# ProDoc_ChisFlash-MBC5-MAX-v1_22_32M.net
KiCad netlist of a schematic drawn in EasyEDA Pro
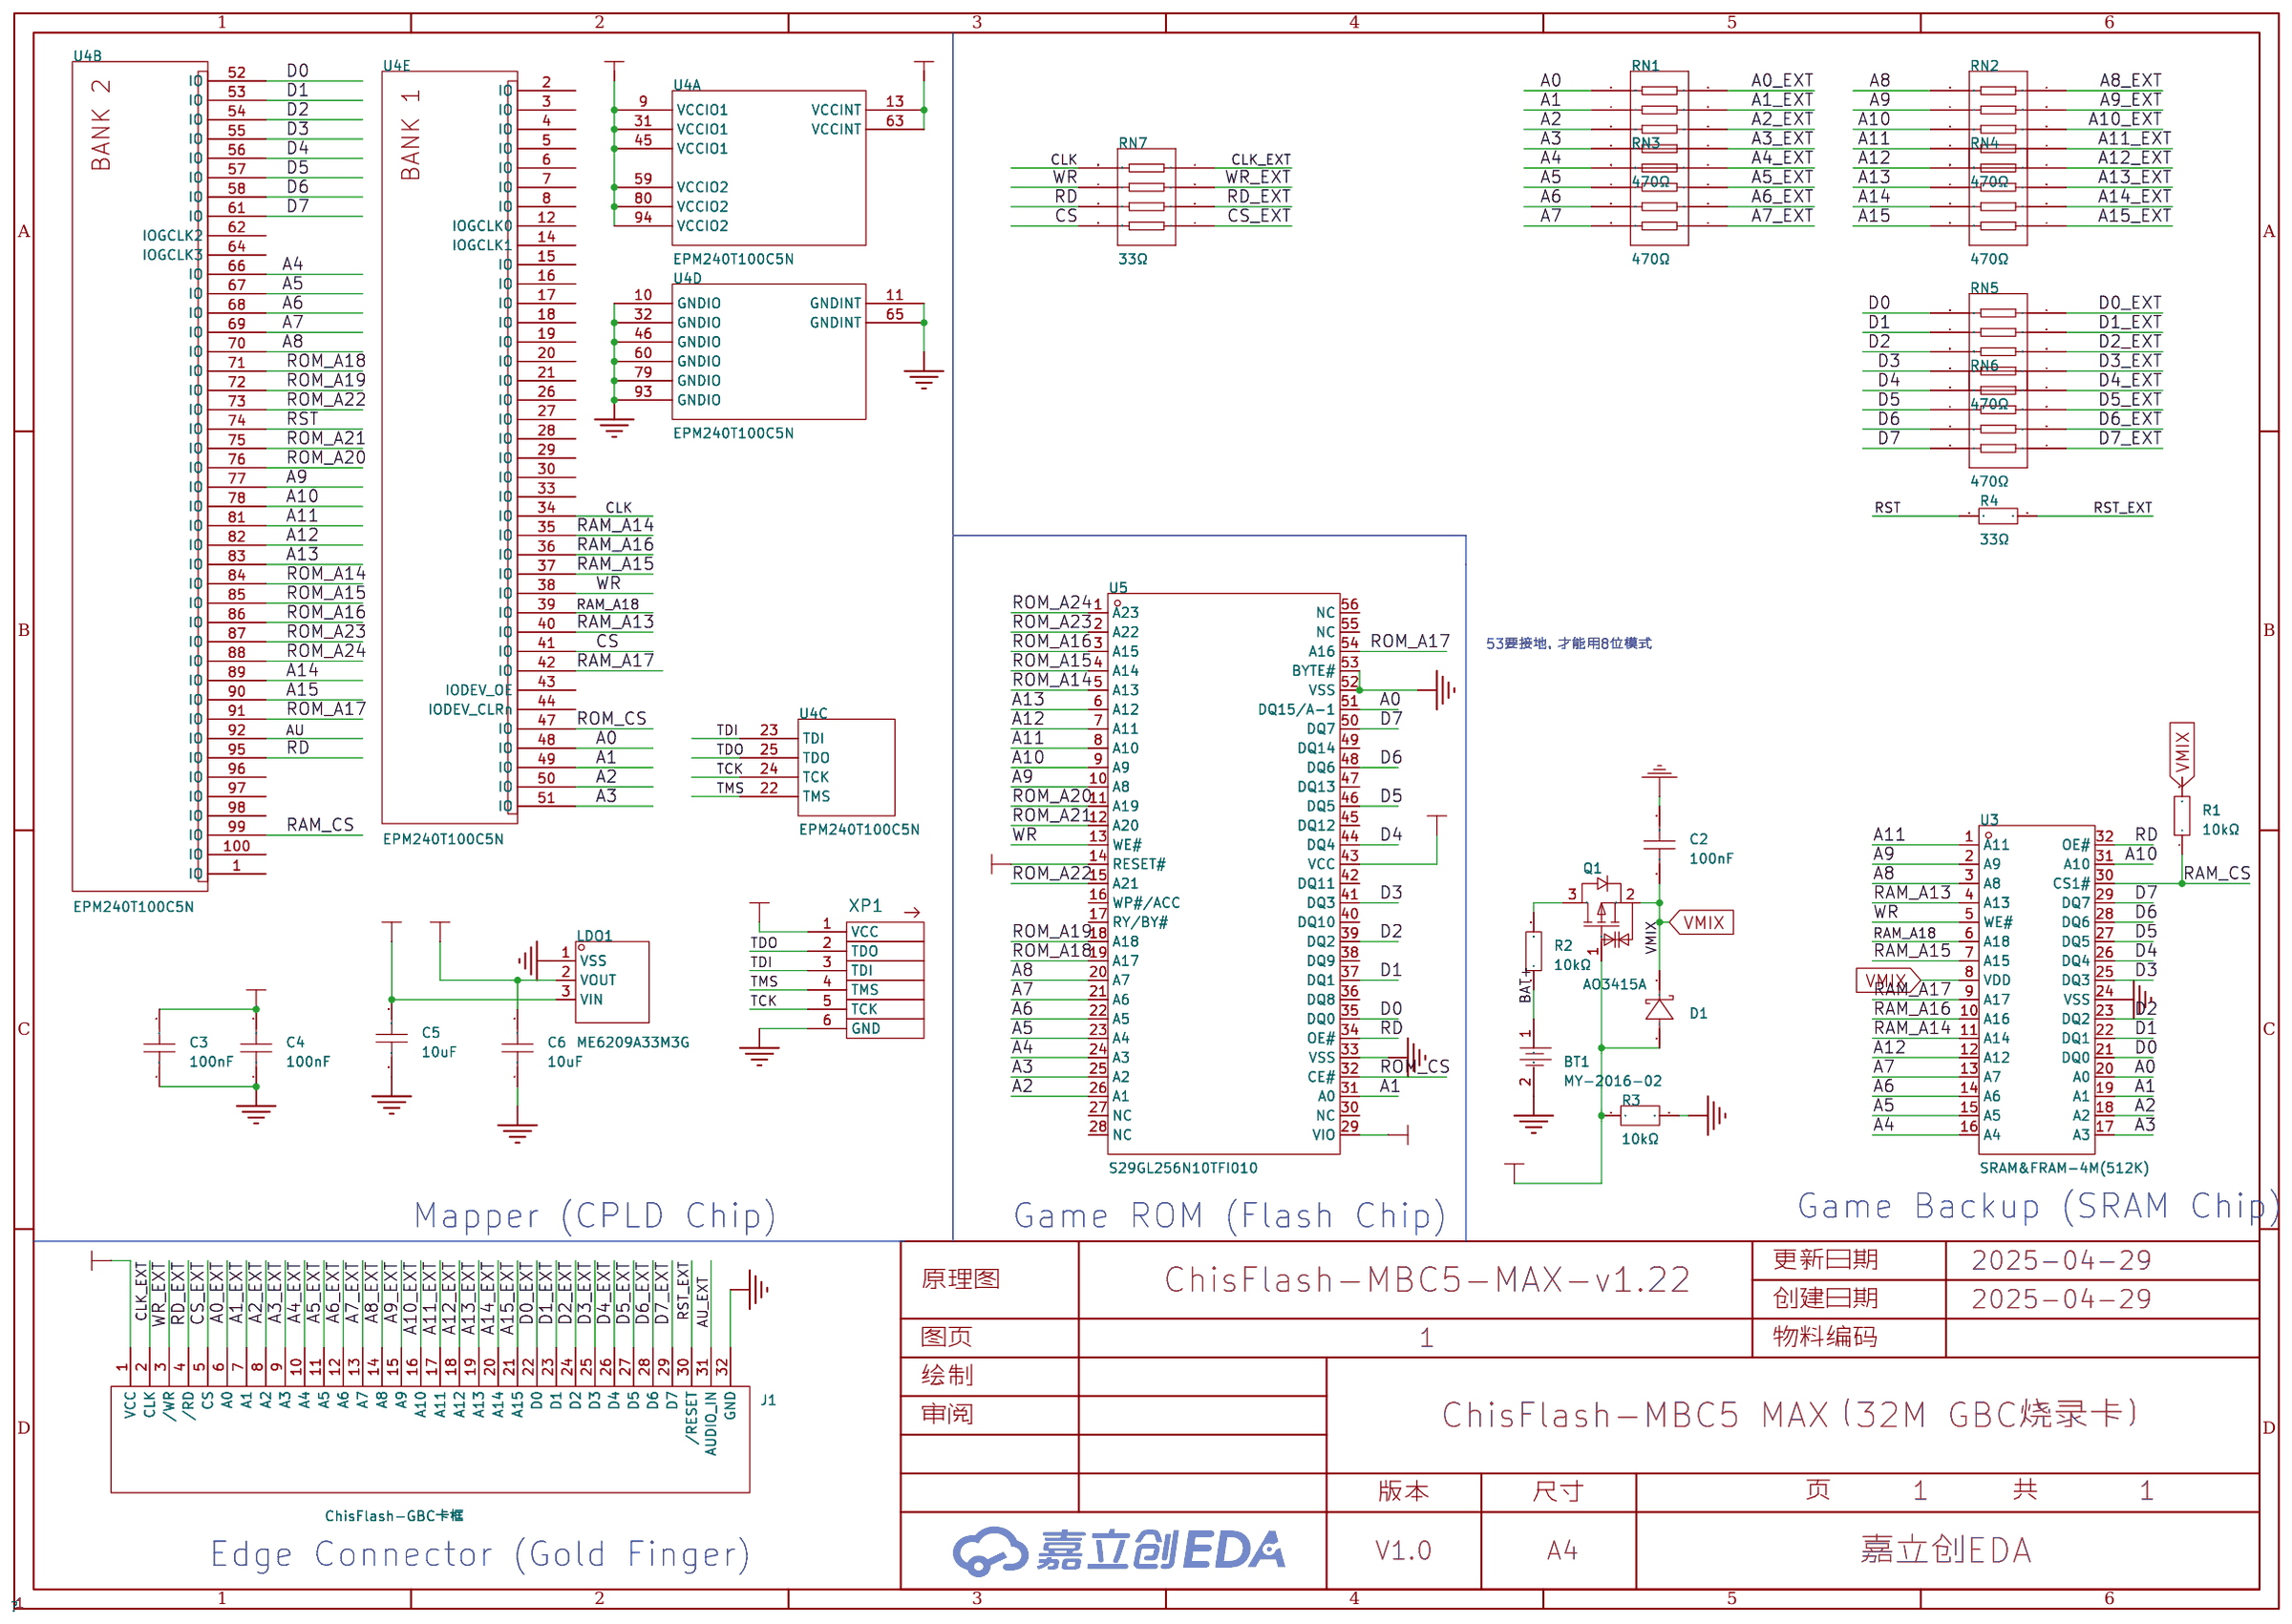
[diagram p0: schematic sheet]

(export (version "E")
  (design (tool "Eeschema 10.0.6"))
  (components
    (comp (ref "BT1")
      (value "MY-2016-02")
      (footprint "easyedapro:BAT-SMD_MY-2032-08")
      (description "连接器类型:电池扣;适用电池规格:CR2016;触头材质:磷青铜;触点电镀:镍;工作温度范围:-25°C~+85°C;")
      (fields (field (name "Manufacturer") "MYOUNG(美阳)"))
      (libsource (lib "easyedapro") (part "MY-2016-02"))
    )
    (comp (ref "C2")
      (value "100nF")
      (footprint "easyedapro:C0603")
      (description "容值:100nF;精度:±10%;额定电压:50V;材质(温度系数):X7R;")
      (fields
        (field (name "Manufacturer Part") "CGA0603X7R104K500JT")
        (field (name "Manufacturer") "HRE(芯声)")
      )
      (libsource (lib "easyedapro") (part "CGA0603X7R104K500JT"))
    )
    (comp (ref "C3")
      (value "100nF")
      (footprint "easyedapro:C0603")
      (description "容值:100nF;精度:±10%;额定电压:50V;材质(温度系数):X7R;")
      (fields
        (field (name "Manufacturer Part") "CGA0603X7R104K500JT")
        (field (name "Manufacturer") "HRE(芯声)")
      )
      (libsource (lib "easyedapro") (part "CGA0603X7R104K500JT"))
    )
    (comp (ref "C4")
      (value "100nF")
      (footprint "easyedapro:C0603")
      (description "容值:100nF;精度:±10%;额定电压:50V;材质(温度系数):X7R;")
      (fields
        (field (name "Manufacturer Part") "CGA0603X7R104K500JT")
        (field (name "Manufacturer") "HRE(芯声)")
      )
      (libsource (lib "easyedapro") (part "CGA0603X7R104K500JT"))
    )
    (comp (ref "C5")
      (value "10uF")
      (footprint "easyedapro:C0603")
      (description "容值:10uF;精度:±20%;额定电压:25V;材质(温度系数):X5R;")
      (fields
        (field (name "Manufacturer Part") "CL10A106MA8NRNC")
        (field (name "Manufacturer") "SAMSUNG(三星)")
      )
      (libsource (lib "easyedapro") (part "CL10A106MA8NRNC"))
    )
    (comp (ref "C6")
      (value "10uF")
      (footprint "easyedapro:C0603")
      (description "容值:10uF;精度:±20%;额定电压:25V;材质(温度系数):X5R;")
      (fields
        (field (name "Manufacturer Part") "CL10A106MA8NRNC")
        (field (name "Manufacturer") "SAMSUNG(三星)")
      )
      (libsource (lib "easyedapro") (part "CL10A106MA8NRNC"))
    )
    (comp (ref "D1")
      (value "RB751V-40")
      (footprint "easyedapro:SOD-323_L1.7-W1.3-LS2.6-RD-1")
      (description "二极管配置:独立式;正向压降(Vf):370mV@1mA;直流反向耐压(Vr):40V;平均整流电流(Io):30mA;")
      (fields (field (name "Manufacturer") "宏迦橙"))
      (libsource (lib "easyedapro") (part "RB751V-40_C7502691"))
    )
    (comp (ref "J1")
      (value "ChisFlash-GBC卡框")
      (footprint "easyedapro:ChisFlash-GBC卡框")
      (libsource (lib "easyedapro") (part "ChisFlash-GBC卡框"))
    )
    (comp (ref "LDO1")
      (value "ME6209A33M3G")
      (footprint "easyedapro:SOT-23-3_L2.9-W1.6-P1.90-LS2.8-BR")
      (description "输出类型:固定;最大输入电压:18V;输出电压:3.3V;最大输出电流:250mA;电源纹波抑制比(PSRR):-;输出极性:正极;")
      (fields (field (name "Manufacturer") "MICRONE(南京微盟)"))
      (libsource (lib "easyedapro") (part "ME6209A33M3G"))
    )
    (comp (ref "Q1")
      (value "AO3415A")
      (footprint "easyedapro:SOT-23-3_L3.0-W1.7-P0.95-LS2.9-BR")
      (fields (field (name "Manufacturer") "UMW(友台半导体)"))
      (libsource (lib "easyedapro") (part "AO3415A_C347479"))
    )
    (comp (ref "R1")
      (value "10kΩ")
      (footprint "easyedapro:R0603")
      (description "电阻类型:厚膜电阻;阻值:10kΩ;精度:±1%;功率:100mW;温度系数:±100ppm/°C;最大工作电压:75V;工作温度范围:-55°C~+155°C;")
      (fields
        (field (name "Manufacturer Part") "0603WAF1002T5E")
        (field (name "Manufacturer") "UNI-ROYAL(厚声)")
      )
      (libsource (lib "easyedapro") (part "0603WAF1002T5E"))
    )
    (comp (ref "R2")
      (value "10kΩ")
      (footprint "easyedapro:R0603")
      (description "电阻类型:厚膜电阻;阻值:10kΩ;精度:±1%;功率:100mW;温度系数:±100ppm/°C;最大工作电压:75V;工作温度范围:-55°C~+155°C;")
      (fields
        (field (name "Manufacturer Part") "0603WAF1002T5E")
        (field (name "Manufacturer") "UNI-ROYAL(厚声)")
      )
      (libsource (lib "easyedapro") (part "0603WAF1002T5E"))
    )
    (comp (ref "R3")
      (value "10kΩ")
      (footprint "easyedapro:R0603")
      (description "电阻类型:薄膜电阻;阻值:10kΩ;精度:±0.1%;功率:100mW;最大工作电压:75V;温度系数:±25ppm/°C;")
      (fields (field (name "Manufacturer Part") "RT0603BRD1010KL") (field (name "Manufacturer") "YAGEO(国巨)"))
      (libsource (lib "easyedapro") (part "RT0603BRD1010KL"))
    )
    (comp (ref "R4")
      (value "33Ω")
      (footprint "easyedapro:R0603")
      (description "电阻类型:厚膜电阻;阻值:33Ω;精度:±1%;功率:100mW;最大工作电压:75V;温度系数:±100ppm/°C;")
      (fields
        (field (name "Manufacturer Part") "0603WAF330JT5E")
        (field (name "Manufacturer") "UNI-ROYAL(厚声)")
      )
      (libsource (lib "easyedapro") (part "0603WAF330JT5E"))
    )
    (comp (ref "RN1")
      (value "470Ω")
      (footprint "easyedapro:RES-ARRAY-SMD_0603-8P-L3.2-W1.6-BL")
      (description "电阻器数:4;阻值:470Ω;精度:±5%;单个元件功率:62.5mW;温度系数:±200ppm/°C;")
      (fields
        (field (name "Manufacturer Part") "4D03WGJ0471T5E")
        (field (name "Manufacturer") "UNI-ROYAL(厚声)")
      )
      (libsource (lib "easyedapro") (part "4D03WGJ0471T5E"))
    )
    (comp (ref "RN2")
      (value "470Ω")
      (footprint "easyedapro:RES-ARRAY-SMD_0603-8P-L3.2-W1.6-BL")
      (description "电阻器数:4;阻值:470Ω;精度:±5%;单个元件功率:62.5mW;温度系数:±200ppm/°C;")
      (fields
        (field (name "Manufacturer Part") "4D03WGJ0471T5E")
        (field (name "Manufacturer") "UNI-ROYAL(厚声)")
      )
      (libsource (lib "easyedapro") (part "4D03WGJ0471T5E"))
    )
    (comp (ref "RN3")
      (value "470Ω")
      (footprint "easyedapro:RES-ARRAY-SMD_0603-8P-L3.2-W1.6-BL")
      (description "电阻器数:4;阻值:470Ω;精度:±5%;单个元件功率:62.5mW;温度系数:±200ppm/°C;")
      (fields
        (field (name "Manufacturer Part") "4D03WGJ0471T5E")
        (field (name "Manufacturer") "UNI-ROYAL(厚声)")
      )
      (libsource (lib "easyedapro") (part "4D03WGJ0471T5E"))
    )
    (comp (ref "RN4")
      (value "470Ω")
      (footprint "easyedapro:RES-ARRAY-SMD_0603-8P-L3.2-W1.6-BL")
      (description "电阻器数:4;阻值:470Ω;精度:±5%;单个元件功率:62.5mW;温度系数:±200ppm/°C;")
      (fields
        (field (name "Manufacturer Part") "4D03WGJ0471T5E")
        (field (name "Manufacturer") "UNI-ROYAL(厚声)")
      )
      (libsource (lib "easyedapro") (part "4D03WGJ0471T5E"))
    )
    (comp (ref "RN5")
      (value "470Ω")
      (footprint "easyedapro:RES-ARRAY-SMD_0603-8P-L3.2-W1.6-BL")
      (description "电阻器数:4;阻值:470Ω;精度:±5%;单个元件功率:62.5mW;温度系数:±200ppm/°C;")
      (fields
        (field (name "Manufacturer Part") "4D03WGJ0471T5E")
        (field (name "Manufacturer") "UNI-ROYAL(厚声)")
      )
      (libsource (lib "easyedapro") (part "4D03WGJ0471T5E"))
    )
    (comp (ref "RN6")
      (value "470Ω")
      (footprint "easyedapro:RES-ARRAY-SMD_0603-8P-L3.2-W1.6-BL")
      (description "电阻器数:4;阻值:470Ω;精度:±5%;单个元件功率:62.5mW;温度系数:±200ppm/°C;")
      (fields
        (field (name "Manufacturer Part") "4D03WGJ0471T5E")
        (field (name "Manufacturer") "UNI-ROYAL(厚声)")
      )
      (libsource (lib "easyedapro") (part "4D03WGJ0471T5E"))
    )
    (comp (ref "RN7")
      (value "33Ω")
      (footprint "easyedapro:RES-ARRAY-SMD_0603-8P-L3.2-W1.6-BL")
      (description "电阻器数:4;阻值:470Ω;精度:±5%;单个元件功率:62.5mW;温度系数:±200ppm/°C;")
      (fields
        (field (name "Manufacturer Part") "4D03WGF330JT5E")
        (field (name "Manufacturer") "UNI-ROYAL(厚声)")
      )
      (libsource (lib "easyedapro") (part "4D03WGJ0471T5E"))
    )
    (comp (ref "U3")
      (value "SRAM&FRAM-4M(512K)")
      (footprint "easyedapro:TSSOP-TSOP二合一_1")
      (libsource (lib "easyedapro") (part "SRAM&FRAM-4M(512K)"))
    )
    (comp (ref "U4")
      (value "EPM240T100C5N")
      (footprint "easyedapro:TQFP-100_L14.0-W14.0-P0.50-LS16.0-BL")
      (description "类型:其它PLD;逻辑门数量:-;逻辑单元数:-;逻辑阵列块数:240;")
      (fields (field (name "Manufacturer") "Intel/Altera"))
      (libsource (lib "easyedapro") (part "EPM240T100C5N"))
    )
    (comp (ref "U5")
      (value "S29GL256N10TFI010")
      (footprint "easyedapro:TSOP-56_L18.4-W14.0-P0.50-LS20.0-TL")
      (libsource (lib "easyedapro") (part "S29GL256N10TFI010"))
    )
    (comp (ref "XP1")
      (value "JTAG")
      (footprint "easyedapro:HDR-TH_6P-P1.27-V-M-1")
      (libsource (lib "easyedapro") (part "jtag"))
    )
  )
  (nets
    (net (code "1") (name "+3V3") (class "Default")
      (node (ref "C3") (pin "2") (pinfunction "2_2") (pintype "unspecified"))
      (node (ref "C4") (pin "2") (pinfunction "2_2") (pintype "unspecified"))
      (node (ref "C6") (pin "2") (pinfunction "2_2") (pintype "unspecified"))
      (node (ref "D1") (pin "2") (pinfunction "A_2") (pintype "unspecified"))
      (node (ref "LDO1") (pin "2") (pinfunction "VOUT_2") (pintype "unspecified"))
      (node (ref "Q1") (pin "1") (pinfunction "G_1") (pintype "unspecified"))
      (node (ref "R3") (pin "1") (pinfunction "1_1") (pintype "unspecified"))
      (node (ref "U4") (pin "13") (pinfunction "VCCINT_13") (pintype "unspecified"))
      (node (ref "U4") (pin "31") (pinfunction "VCCIO1_31") (pintype "unspecified"))
      (node (ref "U4") (pin "45") (pinfunction "VCCIO1_45") (pintype "unspecified"))
      (node (ref "U4") (pin "59") (pinfunction "VCCIO2_59") (pintype "unspecified"))
      (node (ref "U4") (pin "63") (pinfunction "VCCINT_63") (pintype "unspecified"))
      (node (ref "U4") (pin "80") (pinfunction "VCCIO2_80") (pintype "unspecified"))
      (node (ref "U4") (pin "9") (pinfunction "VCCIO1_9") (pintype "unspecified"))
      (node (ref "U4") (pin "94") (pinfunction "VCCIO2_94") (pintype "unspecified"))
      (node (ref "U5") (pin "14") (pinfunction "RESET#_14") (pintype "unspecified"))
      (node (ref "U5") (pin "29") (pinfunction "VIO_29") (pintype "unspecified"))
      (node (ref "U5") (pin "43") (pinfunction "VCC_43") (pintype "unspecified"))
      (node (ref "XP1") (pin "1") (pinfunction "VCC_1") (pintype "output"))
    )
    (net (code "2") (name "+5V") (class "Default")
      (node (ref "C5") (pin "2") (pinfunction "2_2") (pintype "unspecified"))
      (node (ref "J1") (pin "1") (pinfunction "VCC_1") (pintype "unspecified"))
      (node (ref "LDO1") (pin "3") (pinfunction "VIN_3") (pintype "unspecified"))
    )
    (net (code "3") (name "/A0") (class "Default")
      (node (ref "RN1") (pin "8") (pinfunction "8_8") (pintype "input"))
      (node (ref "U3") (pin "20") (pinfunction "A0_20") (pintype "unspecified"))
      (node (ref "U4") (pin "48") (pinfunction "IO_48") (pintype "bidirectional"))
      (node (ref "U5") (pin "51") (pinfunction "DQ15/A-1_51") (pintype "unspecified"))
    )
    (net (code "4") (name "/A0_EXT") (class "Default")
      (node (ref "J1") (pin "6") (pinfunction "A0_6") (pintype "unspecified"))
      (node (ref "RN1") (pin "1") (pinfunction "1_1") (pintype "input"))
    )
    (net (code "5") (name "/A1") (class "Default")
      (node (ref "RN1") (pin "7") (pinfunction "7_7") (pintype "input"))
      (node (ref "U3") (pin "19") (pinfunction "A1_19") (pintype "unspecified"))
      (node (ref "U4") (pin "49") (pinfunction "IO_49") (pintype "bidirectional"))
      (node (ref "U5") (pin "31") (pinfunction "A0_31") (pintype "unspecified"))
    )
    (net (code "6") (name "/A1_EXT") (class "Default")
      (node (ref "J1") (pin "7") (pinfunction "A1_7") (pintype "unspecified"))
      (node (ref "RN1") (pin "2") (pinfunction "2_2") (pintype "input"))
    )
    (net (code "7") (name "/A2") (class "Default")
      (node (ref "RN1") (pin "6") (pinfunction "6_6") (pintype "input"))
      (node (ref "U3") (pin "18") (pinfunction "A2_18") (pintype "unspecified"))
      (node (ref "U4") (pin "50") (pinfunction "IO_50") (pintype "bidirectional"))
      (node (ref "U5") (pin "26") (pinfunction "A1_26") (pintype "unspecified"))
    )
    (net (code "8") (name "/A2_EXT") (class "Default")
      (node (ref "J1") (pin "8") (pinfunction "A2_8") (pintype "unspecified"))
      (node (ref "RN1") (pin "3") (pinfunction "3_3") (pintype "input"))
    )
    (net (code "9") (name "/A3") (class "Default")
      (node (ref "RN1") (pin "5") (pinfunction "5_5") (pintype "input"))
      (node (ref "U3") (pin "17") (pinfunction "A3_17") (pintype "unspecified"))
      (node (ref "U4") (pin "51") (pinfunction "IO_51") (pintype "bidirectional"))
      (node (ref "U5") (pin "25") (pinfunction "A2_25") (pintype "unspecified"))
    )
    (net (code "10") (name "/A3_EXT") (class "Default")
      (node (ref "J1") (pin "9") (pinfunction "A3_9") (pintype "unspecified"))
      (node (ref "RN1") (pin "4") (pinfunction "4_4") (pintype "input"))
    )
    (net (code "11") (name "/A4") (class "Default")
      (node (ref "RN3") (pin "8") (pinfunction "8_8") (pintype "input"))
      (node (ref "U3") (pin "16") (pinfunction "A4_16") (pintype "unspecified"))
      (node (ref "U4") (pin "66") (pinfunction "IO_66") (pintype "bidirectional"))
      (node (ref "U5") (pin "24") (pinfunction "A3_24") (pintype "unspecified"))
    )
    (net (code "12") (name "/A4_EXT") (class "Default")
      (node (ref "J1") (pin "10") (pinfunction "A4_10") (pintype "unspecified"))
      (node (ref "RN3") (pin "1") (pinfunction "1_1") (pintype "input"))
    )
    (net (code "13") (name "/A5") (class "Default")
      (node (ref "RN3") (pin "7") (pinfunction "7_7") (pintype "input"))
      (node (ref "U3") (pin "15") (pinfunction "A5_15") (pintype "unspecified"))
      (node (ref "U4") (pin "67") (pinfunction "IO_67") (pintype "bidirectional"))
      (node (ref "U5") (pin "23") (pinfunction "A4_23") (pintype "unspecified"))
    )
    (net (code "14") (name "/A5_EXT") (class "Default")
      (node (ref "J1") (pin "11") (pinfunction "A5_11") (pintype "unspecified"))
      (node (ref "RN3") (pin "2") (pinfunction "2_2") (pintype "input"))
    )
    (net (code "15") (name "/A6") (class "Default")
      (node (ref "RN3") (pin "6") (pinfunction "6_6") (pintype "input"))
      (node (ref "U3") (pin "14") (pinfunction "A6_14") (pintype "unspecified"))
      (node (ref "U4") (pin "68") (pinfunction "IO_68") (pintype "bidirectional"))
      (node (ref "U5") (pin "22") (pinfunction "A5_22") (pintype "unspecified"))
    )
    (net (code "16") (name "/A6_EXT") (class "Default")
      (node (ref "J1") (pin "12") (pinfunction "A6_12") (pintype "unspecified"))
      (node (ref "RN3") (pin "3") (pinfunction "3_3") (pintype "input"))
    )
    (net (code "17") (name "/A7") (class "Default")
      (node (ref "RN3") (pin "5") (pinfunction "5_5") (pintype "input"))
      (node (ref "U3") (pin "13") (pinfunction "A7_13") (pintype "unspecified"))
      (node (ref "U4") (pin "69") (pinfunction "IO_69") (pintype "bidirectional"))
      (node (ref "U5") (pin "21") (pinfunction "A6_21") (pintype "unspecified"))
    )
    (net (code "18") (name "/A7_EXT") (class "Default")
      (node (ref "J1") (pin "13") (pinfunction "A7_13") (pintype "unspecified"))
      (node (ref "RN3") (pin "4") (pinfunction "4_4") (pintype "input"))
    )
    (net (code "19") (name "/A8") (class "Default")
      (node (ref "RN2") (pin "8") (pinfunction "8_8") (pintype "input"))
      (node (ref "U3") (pin "3") (pinfunction "A8_3") (pintype "unspecified"))
      (node (ref "U4") (pin "70") (pinfunction "IO_70") (pintype "bidirectional"))
      (node (ref "U5") (pin "20") (pinfunction "A7_20") (pintype "unspecified"))
    )
    (net (code "20") (name "/A8_EXT") (class "Default")
      (node (ref "J1") (pin "14") (pinfunction "A8_14") (pintype "unspecified"))
      (node (ref "RN2") (pin "1") (pinfunction "1_1") (pintype "input"))
    )
    (net (code "21") (name "/A9") (class "Default")
      (node (ref "RN2") (pin "7") (pinfunction "7_7") (pintype "input"))
      (node (ref "U3") (pin "2") (pinfunction "A9_2") (pintype "unspecified"))
      (node (ref "U4") (pin "77") (pinfunction "IO_77") (pintype "bidirectional"))
      (node (ref "U5") (pin "10") (pinfunction "A8_10") (pintype "unspecified"))
    )
    (net (code "22") (name "/A9_EXT") (class "Default")
      (node (ref "J1") (pin "15") (pinfunction "A9_15") (pintype "unspecified"))
      (node (ref "RN2") (pin "2") (pinfunction "2_2") (pintype "input"))
    )
    (net (code "23") (name "/A10") (class "Default")
      (node (ref "RN2") (pin "6") (pinfunction "6_6") (pintype "input"))
      (node (ref "U3") (pin "31") (pinfunction "A10_31") (pintype "unspecified"))
      (node (ref "U4") (pin "78") (pinfunction "IO_78") (pintype "bidirectional"))
      (node (ref "U5") (pin "9") (pinfunction "A9_9") (pintype "unspecified"))
    )
    (net (code "24") (name "/A10_EXT") (class "Default")
      (node (ref "J1") (pin "16") (pinfunction "A10_16") (pintype "unspecified"))
      (node (ref "RN2") (pin "3") (pinfunction "3_3") (pintype "input"))
    )
    (net (code "25") (name "/A11") (class "Default")
      (node (ref "RN2") (pin "5") (pinfunction "5_5") (pintype "input"))
      (node (ref "U3") (pin "1") (pinfunction "A11_1") (pintype "unspecified"))
      (node (ref "U4") (pin "81") (pinfunction "IO_81") (pintype "bidirectional"))
      (node (ref "U5") (pin "8") (pinfunction "A10_8") (pintype "unspecified"))
    )
    (net (code "26") (name "/A11_EXT") (class "Default")
      (node (ref "J1") (pin "17") (pinfunction "A11_17") (pintype "unspecified"))
      (node (ref "RN2") (pin "4") (pinfunction "4_4") (pintype "input"))
    )
    (net (code "27") (name "/A12") (class "Default")
      (node (ref "RN4") (pin "8") (pinfunction "8_8") (pintype "input"))
      (node (ref "U3") (pin "12") (pinfunction "A12_12") (pintype "unspecified"))
      (node (ref "U4") (pin "82") (pinfunction "IO_82") (pintype "bidirectional"))
      (node (ref "U5") (pin "7") (pinfunction "A11_7") (pintype "unspecified"))
    )
    (net (code "28") (name "/A12_EXT") (class "Default")
      (node (ref "J1") (pin "18") (pinfunction "A12_18") (pintype "unspecified"))
      (node (ref "RN4") (pin "1") (pinfunction "1_1") (pintype "input"))
    )
    (net (code "29") (name "/A13") (class "Default")
      (node (ref "RN4") (pin "7") (pinfunction "7_7") (pintype "input"))
      (node (ref "U4") (pin "83") (pinfunction "IO_83") (pintype "bidirectional"))
      (node (ref "U5") (pin "6") (pinfunction "A12_6") (pintype "unspecified"))
    )
    (net (code "30") (name "/A13_EXT") (class "Default")
      (node (ref "J1") (pin "19") (pinfunction "A13_19") (pintype "unspecified"))
      (node (ref "RN4") (pin "2") (pinfunction "2_2") (pintype "input"))
    )
    (net (code "31") (name "/A14") (class "Default")
      (node (ref "RN4") (pin "6") (pinfunction "6_6") (pintype "input"))
      (node (ref "U4") (pin "89") (pinfunction "IO_89") (pintype "bidirectional"))
    )
    (net (code "32") (name "/A14_EXT") (class "Default")
      (node (ref "J1") (pin "20") (pinfunction "A14_20") (pintype "unspecified"))
      (node (ref "RN4") (pin "3") (pinfunction "3_3") (pintype "input"))
    )
    (net (code "33") (name "/A15") (class "Default")
      (node (ref "RN4") (pin "5") (pinfunction "5_5") (pintype "input"))
      (node (ref "U4") (pin "90") (pinfunction "IO_90") (pintype "bidirectional"))
    )
    (net (code "34") (name "/A15_EXT") (class "Default")
      (node (ref "J1") (pin "21") (pinfunction "A15_21") (pintype "unspecified"))
      (node (ref "RN4") (pin "4") (pinfunction "4_4") (pintype "input"))
    )
    (net (code "35") (name "/AU") (class "Default")
      (node (ref "U4") (pin "92") (pinfunction "IO_92") (pintype "bidirectional"))
    )
    (net (code "36") (name "/AU_EXT") (class "Default")
      (node (ref "J1") (pin "31") (pinfunction "AUDIO_IN_31") (pintype "unspecified"))
    )
    (net (code "37") (name "/BAT+") (class "Default")
      (node (ref "BT1") (pin "1") (pinfunction "1_1") (pintype "input"))
      (node (ref "R2") (pin "1") (pinfunction "1_1") (pintype "input"))
    )
    (net (code "38") (name "/CLK") (class "Default")
      (node (ref "RN7") (pin "8") (pinfunction "8_8") (pintype "input"))
      (node (ref "U4") (pin "34") (pinfunction "IO_34") (pintype "bidirectional"))
    )
    (net (code "39") (name "/CLK_EXT") (class "Default")
      (node (ref "J1") (pin "2") (pinfunction "CLK_2") (pintype "unspecified"))
      (node (ref "RN7") (pin "1") (pinfunction "1_1") (pintype "input"))
    )
    (net (code "40") (name "/CS") (class "Default")
      (node (ref "RN7") (pin "5") (pinfunction "5_5") (pintype "input"))
      (node (ref "U4") (pin "41") (pinfunction "IO_41") (pintype "bidirectional"))
    )
    (net (code "41") (name "/CS_EXT") (class "Default")
      (node (ref "J1") (pin "5") (pinfunction "CS_5") (pintype "unspecified"))
      (node (ref "RN7") (pin "4") (pinfunction "4_4") (pintype "input"))
    )
    (net (code "42") (name "/D0") (class "Default")
      (node (ref "RN5") (pin "8") (pinfunction "8_8") (pintype "input"))
      (node (ref "U3") (pin "21") (pinfunction "DQ0_21") (pintype "unspecified"))
      (node (ref "U4") (pin "52") (pinfunction "IO_52") (pintype "bidirectional"))
      (node (ref "U5") (pin "35") (pinfunction "DQ0_35") (pintype "unspecified"))
    )
    (net (code "43") (name "/D0_EXT") (class "Default")
      (node (ref "J1") (pin "22") (pinfunction "D0_22") (pintype "unspecified"))
      (node (ref "RN5") (pin "1") (pinfunction "1_1") (pintype "input"))
    )
    (net (code "44") (name "/D1") (class "Default")
      (node (ref "RN5") (pin "7") (pinfunction "7_7") (pintype "input"))
      (node (ref "U3") (pin "22") (pinfunction "DQ1_22") (pintype "unspecified"))
      (node (ref "U4") (pin "53") (pinfunction "IO_53") (pintype "bidirectional"))
      (node (ref "U5") (pin "37") (pinfunction "DQ1_37") (pintype "unspecified"))
    )
    (net (code "45") (name "/D1_EXT") (class "Default")
      (node (ref "J1") (pin "23") (pinfunction "D1_23") (pintype "unspecified"))
      (node (ref "RN5") (pin "2") (pinfunction "2_2") (pintype "input"))
    )
    (net (code "46") (name "/D2") (class "Default")
      (node (ref "RN5") (pin "6") (pinfunction "6_6") (pintype "input"))
      (node (ref "U3") (pin "23") (pinfunction "DQ2_23") (pintype "unspecified"))
      (node (ref "U4") (pin "54") (pinfunction "IO_54") (pintype "bidirectional"))
      (node (ref "U5") (pin "39") (pinfunction "DQ2_39") (pintype "unspecified"))
    )
    (net (code "47") (name "/D2_EXT") (class "Default")
      (node (ref "J1") (pin "24") (pinfunction "D2_24") (pintype "unspecified"))
      (node (ref "RN5") (pin "3") (pinfunction "3_3") (pintype "input"))
    )
    (net (code "48") (name "/D3") (class "Default")
      (node (ref "RN5") (pin "5") (pinfunction "5_5") (pintype "input"))
      (node (ref "U3") (pin "25") (pinfunction "DQ3_25") (pintype "unspecified"))
      (node (ref "U4") (pin "55") (pinfunction "IO_55") (pintype "bidirectional"))
      (node (ref "U5") (pin "41") (pinfunction "DQ3_41") (pintype "unspecified"))
    )
    (net (code "49") (name "/D3_EXT") (class "Default")
      (node (ref "J1") (pin "25") (pinfunction "D3_25") (pintype "unspecified"))
      (node (ref "RN5") (pin "4") (pinfunction "4_4") (pintype "input"))
    )
    (net (code "50") (name "/D4") (class "Default")
      (node (ref "RN6") (pin "8") (pinfunction "8_8") (pintype "input"))
      (node (ref "U3") (pin "26") (pinfunction "DQ4_26") (pintype "unspecified"))
      (node (ref "U4") (pin "56") (pinfunction "IO_56") (pintype "bidirectional"))
      (node (ref "U5") (pin "44") (pinfunction "DQ4_44") (pintype "unspecified"))
    )
    (net (code "51") (name "/D4_EXT") (class "Default")
      (node (ref "J1") (pin "26") (pinfunction "D4_26") (pintype "unspecified"))
      (node (ref "RN6") (pin "1") (pinfunction "1_1") (pintype "input"))
    )
    (net (code "52") (name "/D5") (class "Default")
      (node (ref "RN6") (pin "7") (pinfunction "7_7") (pintype "input"))
      (node (ref "U3") (pin "27") (pinfunction "DQ5_27") (pintype "unspecified"))
      (node (ref "U4") (pin "57") (pinfunction "IO_57") (pintype "bidirectional"))
      (node (ref "U5") (pin "46") (pinfunction "DQ5_46") (pintype "unspecified"))
    )
    (net (code "53") (name "/D5_EXT") (class "Default")
      (node (ref "J1") (pin "27") (pinfunction "D5_27") (pintype "unspecified"))
      (node (ref "RN6") (pin "2") (pinfunction "2_2") (pintype "input"))
    )
    (net (code "54") (name "/D6") (class "Default")
      (node (ref "RN6") (pin "6") (pinfunction "6_6") (pintype "input"))
      (node (ref "U3") (pin "28") (pinfunction "DQ6_28") (pintype "unspecified"))
      (node (ref "U4") (pin "58") (pinfunction "IO_58") (pintype "bidirectional"))
      (node (ref "U5") (pin "48") (pinfunction "DQ6_48") (pintype "unspecified"))
    )
    (net (code "55") (name "/D6_EXT") (class "Default")
      (node (ref "J1") (pin "28") (pinfunction "D6_28") (pintype "unspecified"))
      (node (ref "RN6") (pin "3") (pinfunction "3_3") (pintype "input"))
    )
    (net (code "56") (name "/D7") (class "Default")
      (node (ref "RN6") (pin "5") (pinfunction "5_5") (pintype "input"))
      (node (ref "U3") (pin "29") (pinfunction "DQ7_29") (pintype "unspecified"))
      (node (ref "U4") (pin "61") (pinfunction "IO_61") (pintype "bidirectional"))
      (node (ref "U5") (pin "50") (pinfunction "DQ7_50") (pintype "unspecified"))
    )
    (net (code "57") (name "/D7_EXT") (class "Default")
      (node (ref "J1") (pin "29") (pinfunction "D7_29") (pintype "unspecified"))
      (node (ref "RN6") (pin "4") (pinfunction "4_4") (pintype "input"))
    )
    (net (code "58") (name "/RAM_A13") (class "Default")
      (node (ref "U3") (pin "4") (pinfunction "A13_4") (pintype "unspecified"))
      (node (ref "U4") (pin "40") (pinfunction "IO_40") (pintype "bidirectional"))
    )
    (net (code "59") (name "/RAM_A14") (class "Default")
      (node (ref "U3") (pin "11") (pinfunction "A14_11") (pintype "unspecified"))
      (node (ref "U4") (pin "35") (pinfunction "IO_35") (pintype "bidirectional"))
    )
    (net (code "60") (name "/RAM_A15") (class "Default")
      (node (ref "U3") (pin "7") (pinfunction "A15_7") (pintype "unspecified"))
      (node (ref "U4") (pin "37") (pinfunction "IO_37") (pintype "bidirectional"))
    )
    (net (code "61") (name "/RAM_A16") (class "Default")
      (node (ref "U3") (pin "10") (pinfunction "A16_10") (pintype "unspecified"))
      (node (ref "U4") (pin "36") (pinfunction "IO_36") (pintype "bidirectional"))
    )
    (net (code "62") (name "/RAM_A17") (class "Default")
      (node (ref "U3") (pin "9") (pinfunction "A17_9") (pintype "unspecified"))
      (node (ref "U4") (pin "42") (pinfunction "IO_42") (pintype "bidirectional"))
    )
    (net (code "63") (name "/RAM_A18") (class "Default")
      (node (ref "U3") (pin "6") (pinfunction "A18_6") (pintype "unspecified"))
      (node (ref "U4") (pin "39") (pinfunction "IO_39") (pintype "bidirectional"))
    )
    (net (code "64") (name "/RAM_CS") (class "Default")
      (node (ref "R1") (pin "1") (pinfunction "1_1") (pintype "input"))
      (node (ref "U3") (pin "30") (pinfunction "CS1#_30") (pintype "unspecified"))
      (node (ref "U4") (pin "99") (pinfunction "IO_99") (pintype "bidirectional"))
    )
    (net (code "65") (name "/RD") (class "Default")
      (node (ref "RN7") (pin "6") (pinfunction "6_6") (pintype "input"))
      (node (ref "U3") (pin "32") (pinfunction "OE#_32") (pintype "unspecified"))
      (node (ref "U4") (pin "95") (pinfunction "IO_95") (pintype "bidirectional"))
      (node (ref "U5") (pin "34") (pinfunction "OE#_34") (pintype "unspecified"))
    )
    (net (code "66") (name "/RD_EXT") (class "Default")
      (node (ref "J1") (pin "4") (pinfunction "/RD_4") (pintype "unspecified"))
      (node (ref "RN7") (pin "3") (pinfunction "3_3") (pintype "input"))
    )
    (net (code "67") (name "/ROM_A14") (class "Default")
      (node (ref "U4") (pin "84") (pinfunction "IO_84") (pintype "bidirectional"))
      (node (ref "U5") (pin "5") (pinfunction "A13_5") (pintype "unspecified"))
    )
    (net (code "68") (name "/ROM_A15") (class "Default")
      (node (ref "U4") (pin "85") (pinfunction "IO_85") (pintype "bidirectional"))
      (node (ref "U5") (pin "4") (pinfunction "A14_4") (pintype "unspecified"))
    )
    (net (code "69") (name "/ROM_A16") (class "Default")
      (node (ref "U4") (pin "86") (pinfunction "IO_86") (pintype "bidirectional"))
      (node (ref "U5") (pin "3") (pinfunction "A15_3") (pintype "unspecified"))
    )
    (net (code "70") (name "/ROM_A17") (class "Default")
      (node (ref "U4") (pin "91") (pinfunction "IO_91") (pintype "bidirectional"))
      (node (ref "U5") (pin "54") (pinfunction "A16_54") (pintype "unspecified"))
    )
    (net (code "71") (name "/ROM_A18") (class "Default")
      (node (ref "U4") (pin "71") (pinfunction "IO_71") (pintype "bidirectional"))
      (node (ref "U5") (pin "19") (pinfunction "A17_19") (pintype "unspecified"))
    )
    (net (code "72") (name "/ROM_A19") (class "Default")
      (node (ref "U4") (pin "72") (pinfunction "IO_72") (pintype "bidirectional"))
      (node (ref "U5") (pin "18") (pinfunction "A18_18") (pintype "unspecified"))
    )
    (net (code "73") (name "/ROM_A20") (class "Default")
      (node (ref "U4") (pin "76") (pinfunction "IO_76") (pintype "bidirectional"))
      (node (ref "U5") (pin "11") (pinfunction "A19_11") (pintype "unspecified"))
    )
    (net (code "74") (name "/ROM_A21") (class "Default")
      (node (ref "U4") (pin "75") (pinfunction "IO_75") (pintype "bidirectional"))
      (node (ref "U5") (pin "12") (pinfunction "A20_12") (pintype "unspecified"))
    )
    (net (code "75") (name "/ROM_A22") (class "Default")
      (node (ref "U4") (pin "73") (pinfunction "IO_73") (pintype "bidirectional"))
      (node (ref "U5") (pin "15") (pinfunction "A21_15") (pintype "unspecified"))
    )
    (net (code "76") (name "/ROM_A23") (class "Default")
      (node (ref "U4") (pin "87") (pinfunction "IO_87") (pintype "bidirectional"))
      (node (ref "U5") (pin "2") (pinfunction "A22_2") (pintype "unspecified"))
    )
    (net (code "77") (name "/ROM_A24") (class "Default")
      (node (ref "U4") (pin "88") (pinfunction "IO_88") (pintype "bidirectional"))
      (node (ref "U5") (pin "1") (pinfunction "A23_1") (pintype "unspecified"))
    )
    (net (code "78") (name "/ROM_CS") (class "Default")
      (node (ref "U4") (pin "47") (pinfunction "IO_47") (pintype "bidirectional"))
      (node (ref "U5") (pin "32") (pinfunction "CE#_32") (pintype "unspecified"))
    )
    (net (code "79") (name "/RST") (class "Default")
      (node (ref "R4") (pin "1") (pinfunction "1_1") (pintype "input"))
      (node (ref "U4") (pin "74") (pinfunction "IO_74") (pintype "bidirectional"))
    )
    (net (code "80") (name "/RST_EXT") (class "Default")
      (node (ref "J1") (pin "30") (pinfunction "/RESET_30") (pintype "unspecified"))
      (node (ref "R4") (pin "2") (pinfunction "2_2") (pintype "input"))
    )
    (net (code "81") (name "/TCK") (class "Default")
      (node (ref "U4") (pin "24") (pinfunction "TCK_24") (pintype "unspecified"))
      (node (ref "XP1") (pin "5") (pinfunction "TCK_5") (pintype "input"))
    )
    (net (code "82") (name "/TDI") (class "Default")
      (node (ref "U4") (pin "23") (pinfunction "TDI_23") (pintype "unspecified"))
      (node (ref "XP1") (pin "3") (pinfunction "TDI_3") (pintype "output"))
    )
    (net (code "83") (name "/TDO") (class "Default")
      (node (ref "U4") (pin "25") (pinfunction "TDO_25") (pintype "output"))
      (node (ref "XP1") (pin "2") (pinfunction "TDO_2") (pintype "output"))
    )
    (net (code "84") (name "/TMS") (class "Default")
      (node (ref "U4") (pin "22") (pinfunction "TMS_22") (pintype "unspecified"))
      (node (ref "XP1") (pin "4") (pinfunction "TMS_4") (pintype "output"))
    )
    (net (code "85") (name "/WR") (class "Default")
      (node (ref "RN7") (pin "7") (pinfunction "7_7") (pintype "input"))
      (node (ref "U3") (pin "5") (pinfunction "WE#_5") (pintype "unspecified"))
      (node (ref "U4") (pin "38") (pinfunction "IO_38") (pintype "bidirectional"))
      (node (ref "U5") (pin "13") (pinfunction "WE#_13") (pintype "unspecified"))
    )
    (net (code "86") (name "/WR_EXT") (class "Default")
      (node (ref "J1") (pin "3") (pinfunction "/WR_3") (pintype "unspecified"))
      (node (ref "RN7") (pin "2") (pinfunction "2_2") (pintype "input"))
    )
    (net (code "87") (name "GND") (class "Default")
      (node (ref "BT1") (pin "2") (pinfunction "2_2") (pintype "input"))
      (node (ref "C2") (pin "1") (pinfunction "1_1") (pintype "unspecified"))
      (node (ref "C3") (pin "1") (pinfunction "1_1") (pintype "unspecified"))
      (node (ref "C4") (pin "1") (pinfunction "1_1") (pintype "unspecified"))
      (node (ref "C5") (pin "1") (pinfunction "1_1") (pintype "unspecified"))
      (node (ref "C6") (pin "1") (pinfunction "1_1") (pintype "unspecified"))
      (node (ref "J1") (pin "32") (pinfunction "GND_32") (pintype "unspecified"))
      (node (ref "LDO1") (pin "1") (pinfunction "VSS_1") (pintype "unspecified"))
      (node (ref "R3") (pin "2") (pinfunction "2_2") (pintype "unspecified"))
      (node (ref "U3") (pin "24") (pinfunction "VSS_24") (pintype "unspecified"))
      (node (ref "U4") (pin "10") (pinfunction "GNDIO_10") (pintype "unspecified"))
      (node (ref "U4") (pin "11") (pinfunction "GNDINT_11") (pintype "unspecified"))
      (node (ref "U4") (pin "32") (pinfunction "GNDIO_32") (pintype "unspecified"))
      (node (ref "U4") (pin "46") (pinfunction "GNDIO_46") (pintype "unspecified"))
      (node (ref "U4") (pin "60") (pinfunction "GNDIO_60") (pintype "unspecified"))
      (node (ref "U4") (pin "65") (pinfunction "GNDINT_65") (pintype "unspecified"))
      (node (ref "U4") (pin "79") (pinfunction "GNDIO_79") (pintype "unspecified"))
      (node (ref "U4") (pin "93") (pinfunction "GNDIO_93") (pintype "unspecified"))
      (node (ref "U5") (pin "33") (pinfunction "VSS_33") (pintype "unspecified"))
      (node (ref "U5") (pin "52") (pinfunction "VSS_52") (pintype "unspecified"))
      (node (ref "U5") (pin "53") (pinfunction "BYTE#_53") (pintype "unspecified"))
      (node (ref "XP1") (pin "6") (pinfunction "GND_6") (pintype "input"))
    )
    (net (code "88") (name "Net-(Q1-D)") (class "Default")
      (node (ref "Q1") (pin "3") (pinfunction "D_3") (pintype "unspecified"))
      (node (ref "R2") (pin "2") (pinfunction "2_2") (pintype "input"))
    )
    (net (code "89") (name "VMIX") (class "Default")
      (node (ref "C2") (pin "2") (pinfunction "2_2") (pintype "unspecified"))
      (node (ref "D1") (pin "1") (pinfunction "K_1") (pintype "unspecified"))
      (node (ref "Q1") (pin "2") (pinfunction "S_2") (pintype "unspecified"))
      (node (ref "R1") (pin "2") (pinfunction "2_2") (pintype "input"))
      (node (ref "U3") (pin "8") (pinfunction "VDD_8") (pintype "unspecified"))
    )
    (net (code "90") (name "unconnected-(U4B-IO-Pad1)") (class "Default")
      (node (ref "U4") (pin "1") (pinfunction "IO_1") (pintype "bidirectional"))
    )
    (net (code "91") (name "unconnected-(U4B-IO-Pad96)") (class "Default")
      (node (ref "U4") (pin "96") (pinfunction "IO_96") (pintype "bidirectional"))
    )
    (net (code "92") (name "unconnected-(U4B-IO-Pad97)") (class "Default")
      (node (ref "U4") (pin "97") (pinfunction "IO_97") (pintype "bidirectional"))
    )
    (net (code "93") (name "unconnected-(U4B-IO-Pad98)") (class "Default")
      (node (ref "U4") (pin "98") (pinfunction "IO_98") (pintype "bidirectional"))
    )
    (net (code "94") (name "unconnected-(U4B-IO-Pad100)") (class "Default")
      (node (ref "U4") (pin "100") (pinfunction "IO_100") (pintype "bidirectional"))
    )
    (net (code "95") (name "unconnected-(U4B-IOGCLK2-Pad62)") (class "Default")
      (node (ref "U4") (pin "62") (pinfunction "IOGCLK2_62") (pintype "bidirectional"))
    )
    (net (code "96") (name "unconnected-(U4B-IOGCLK3-Pad64)") (class "Default")
      (node (ref "U4") (pin "64") (pinfunction "IOGCLK3_64") (pintype "bidirectional"))
    )
    (net (code "97") (name "unconnected-(U4E-IO-Pad2)") (class "Default")
      (node (ref "U4") (pin "2") (pinfunction "IO_2") (pintype "bidirectional"))
    )
    (net (code "98") (name "unconnected-(U4E-IO-Pad3)") (class "Default")
      (node (ref "U4") (pin "3") (pinfunction "IO_3") (pintype "bidirectional"))
    )
    (net (code "99") (name "unconnected-(U4E-IO-Pad4)") (class "Default")
      (node (ref "U4") (pin "4") (pinfunction "IO_4") (pintype "bidirectional"))
    )
    (net (code "100") (name "unconnected-(U4E-IO-Pad5)") (class "Default")
      (node (ref "U4") (pin "5") (pinfunction "IO_5") (pintype "bidirectional"))
    )
    (net (code "101") (name "unconnected-(U4E-IO-Pad6)") (class "Default")
      (node (ref "U4") (pin "6") (pinfunction "IO_6") (pintype "bidirectional"))
    )
    (net (code "102") (name "unconnected-(U4E-IO-Pad7)") (class "Default")
      (node (ref "U4") (pin "7") (pinfunction "IO_7") (pintype "bidirectional"))
    )
    (net (code "103") (name "unconnected-(U4E-IO-Pad8)") (class "Default")
      (node (ref "U4") (pin "8") (pinfunction "IO_8") (pintype "bidirectional"))
    )
    (net (code "104") (name "unconnected-(U4E-IO-Pad15)") (class "Default")
      (node (ref "U4") (pin "15") (pinfunction "IO_15") (pintype "bidirectional"))
    )
    (net (code "105") (name "unconnected-(U4E-IO-Pad16)") (class "Default")
      (node (ref "U4") (pin "16") (pinfunction "IO_16") (pintype "bidirectional"))
    )
    (net (code "106") (name "unconnected-(U4E-IO-Pad17)") (class "Default")
      (node (ref "U4") (pin "17") (pinfunction "IO_17") (pintype "bidirectional"))
    )
    (net (code "107") (name "unconnected-(U4E-IO-Pad18)") (class "Default")
      (node (ref "U4") (pin "18") (pinfunction "IO_18") (pintype "bidirectional"))
    )
    (net (code "108") (name "unconnected-(U4E-IO-Pad19)") (class "Default")
      (node (ref "U4") (pin "19") (pinfunction "IO_19") (pintype "bidirectional"))
    )
    (net (code "109") (name "unconnected-(U4E-IO-Pad20)") (class "Default")
      (node (ref "U4") (pin "20") (pinfunction "IO_20") (pintype "bidirectional"))
    )
    (net (code "110") (name "unconnected-(U4E-IO-Pad21)") (class "Default")
      (node (ref "U4") (pin "21") (pinfunction "IO_21") (pintype "bidirectional"))
    )
    (net (code "111") (name "unconnected-(U4E-IO-Pad26)") (class "Default")
      (node (ref "U4") (pin "26") (pinfunction "IO_26") (pintype "bidirectional"))
    )
    (net (code "112") (name "unconnected-(U4E-IO-Pad27)") (class "Default")
      (node (ref "U4") (pin "27") (pinfunction "IO_27") (pintype "bidirectional"))
    )
    (net (code "113") (name "unconnected-(U4E-IO-Pad28)") (class "Default")
      (node (ref "U4") (pin "28") (pinfunction "IO_28") (pintype "bidirectional"))
    )
    (net (code "114") (name "unconnected-(U4E-IO-Pad29)") (class "Default")
      (node (ref "U4") (pin "29") (pinfunction "IO_29") (pintype "bidirectional"))
    )
    (net (code "115") (name "unconnected-(U4E-IO-Pad30)") (class "Default")
      (node (ref "U4") (pin "30") (pinfunction "IO_30") (pintype "bidirectional"))
    )
    (net (code "116") (name "unconnected-(U4E-IO-Pad33)") (class "Default")
      (node (ref "U4") (pin "33") (pinfunction "IO_33") (pintype "bidirectional"))
    )
    (net (code "117") (name "unconnected-(U4E-IODEV_CLRn-Pad44)") (class "Default")
      (node (ref "U4") (pin "44") (pinfunction "IODEV_CLRn_44") (pintype "bidirectional"))
    )
    (net (code "118") (name "unconnected-(U4E-IODEV_OE-Pad43)") (class "Default")
      (node (ref "U4") (pin "43") (pinfunction "IODEV_OE_43") (pintype "bidirectional"))
    )
    (net (code "119") (name "unconnected-(U4E-IOGCLK0-Pad12)") (class "Default")
      (node (ref "U4") (pin "12") (pinfunction "IOGCLK0_12") (pintype "bidirectional"))
    )
    (net (code "120") (name "unconnected-(U4E-IOGCLK1-Pad14)") (class "Default")
      (node (ref "U4") (pin "14") (pinfunction "IOGCLK1_14") (pintype "bidirectional"))
    )
    (net (code "121") (name "unconnected-(U5-DQ8-Pad36)") (class "Default")
      (node (ref "U5") (pin "36") (pinfunction "DQ8_36") (pintype "unspecified"))
    )
    (net (code "122") (name "unconnected-(U5-DQ9-Pad38)") (class "Default")
      (node (ref "U5") (pin "38") (pinfunction "DQ9_38") (pintype "unspecified"))
    )
    (net (code "123") (name "unconnected-(U5-DQ10-Pad40)") (class "Default")
      (node (ref "U5") (pin "40") (pinfunction "DQ10_40") (pintype "unspecified"))
    )
    (net (code "124") (name "unconnected-(U5-DQ11-Pad42)") (class "Default")
      (node (ref "U5") (pin "42") (pinfunction "DQ11_42") (pintype "unspecified"))
    )
    (net (code "125") (name "unconnected-(U5-DQ12-Pad45)") (class "Default")
      (node (ref "U5") (pin "45") (pinfunction "DQ12_45") (pintype "unspecified"))
    )
    (net (code "126") (name "unconnected-(U5-DQ13-Pad47)") (class "Default")
      (node (ref "U5") (pin "47") (pinfunction "DQ13_47") (pintype "unspecified"))
    )
    (net (code "127") (name "unconnected-(U5-DQ14-Pad49)") (class "Default")
      (node (ref "U5") (pin "49") (pinfunction "DQ14_49") (pintype "unspecified"))
    )
    (net (code "128") (name "unconnected-(U5-NC-Pad27)") (class "Default")
      (node (ref "U5") (pin "27") (pinfunction "NC_27") (pintype "unspecified"))
    )
    (net (code "129") (name "unconnected-(U5-NC-Pad28)") (class "Default")
      (node (ref "U5") (pin "28") (pinfunction "NC_28") (pintype "unspecified"))
    )
    (net (code "130") (name "unconnected-(U5-NC-Pad30)") (class "Default")
      (node (ref "U5") (pin "30") (pinfunction "NC_30") (pintype "unspecified"))
    )
    (net (code "131") (name "unconnected-(U5-NC-Pad55)") (class "Default")
      (node (ref "U5") (pin "55") (pinfunction "NC_55") (pintype "unspecified"))
    )
    (net (code "132") (name "unconnected-(U5-NC-Pad56)") (class "Default")
      (node (ref "U5") (pin "56") (pinfunction "NC_56") (pintype "unspecified"))
    )
    (net (code "133") (name "unconnected-(U5-RY{slash}BY#-Pad17)") (class "Default")
      (node (ref "U5") (pin "17") (pinfunction "RY/BY#_17") (pintype "unspecified"))
    )
    (net (code "134") (name "unconnected-(U5-WP#{slash}ACC-Pad16)") (class "Default")
      (node (ref "U5") (pin "16") (pinfunction "WP#/ACC_16") (pintype "unspecified"))
    )
  )
)
